# buck_boost.net
KiCad netlist of a schematic drawn in Altium Designer
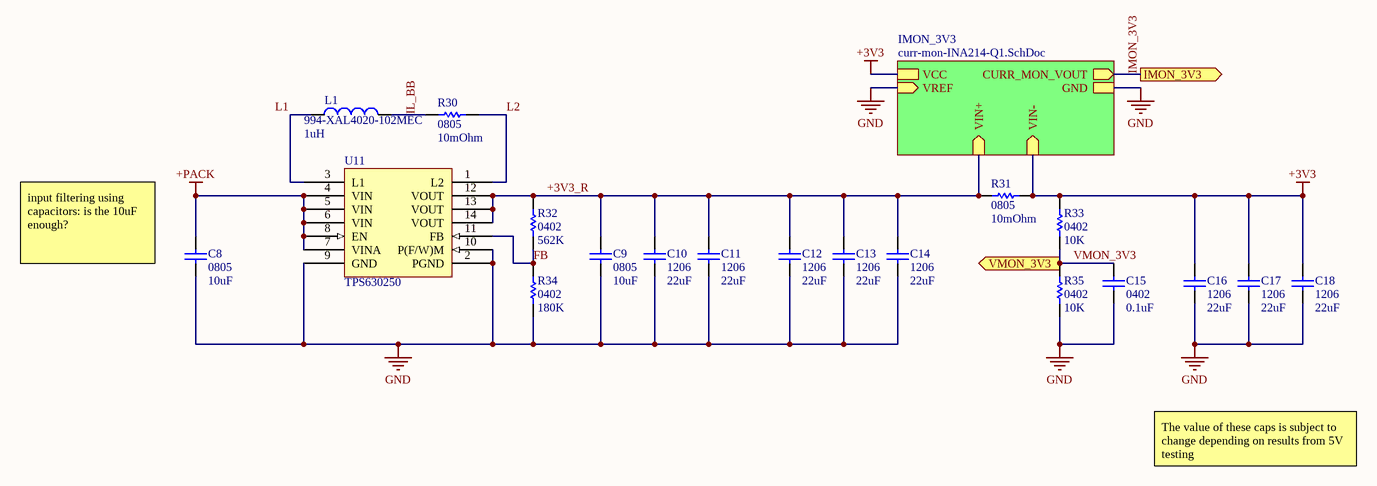
[diagram p0: buck_boost.SchDoc]

(export (version "E")
  (design (tool "Eeschema 10.0.6"))
  (components
    (comp (ref "C8")
      (value "0805")
      (footprint "CAP0805R")
      (description "0805 capacitor")
      (fields (field (name "ALTIUM_VALUE") "10uF"))
      (libsource (lib "heron-general") (part "CAP0805"))
    )
    (comp (ref "C9")
      (value "0805")
      (footprint "CAP0805R")
      (description "0805 capacitor")
      (fields (field (name "ALTIUM_VALUE") "10uF"))
      (libsource (lib "heron-general") (part "CAP0805"))
    )
    (comp (ref "C10")
      (value "1206")
      (footprint "CAP1206R")
      (description "1206 capacitor")
      (fields (field (name "ALTIUM_VALUE") "22uF"))
      (libsource (lib "heron-general") (part "CAP1206"))
    )
    (comp (ref "C11")
      (value "1206")
      (footprint "CAP1206R")
      (description "1206 capacitor")
      (fields (field (name "ALTIUM_VALUE") "22uF"))
      (libsource (lib "heron-general") (part "CAP1206"))
    )
    (comp (ref "C12")
      (value "1206")
      (footprint "CAP1206R")
      (description "1206 capacitor")
      (fields (field (name "ALTIUM_VALUE") "22uF"))
      (libsource (lib "heron-general") (part "CAP1206"))
    )
    (comp (ref "C13")
      (value "1206")
      (footprint "CAP1206R")
      (description "1206 capacitor")
      (fields (field (name "ALTIUM_VALUE") "22uF"))
      (libsource (lib "heron-general") (part "CAP1206"))
    )
    (comp (ref "C14")
      (value "1206")
      (footprint "CAP1206R")
      (description "1206 capacitor")
      (fields (field (name "ALTIUM_VALUE") "22uF"))
      (libsource (lib "heron-general") (part "CAP1206"))
    )
    (comp (ref "C15")
      (value "0402")
      (footprint "CAP0402R")
      (description "0402 capacitor")
      (fields (field (name "ALTIUM_VALUE") "0.1uF"))
      (libsource (lib "heron-general") (part "CAP0402"))
    )
    (comp (ref "C16")
      (value "1206")
      (footprint "CAP1206R")
      (description "1206 capacitor")
      (fields (field (name "ALTIUM_VALUE") "22uF"))
      (libsource (lib "heron-general") (part "CAP1206"))
    )
    (comp (ref "C17")
      (value "1206")
      (footprint "CAP1206R")
      (description "1206 capacitor")
      (fields (field (name "ALTIUM_VALUE") "22uF"))
      (libsource (lib "heron-general") (part "CAP1206"))
    )
    (comp (ref "C18")
      (value "1206")
      (footprint "CAP1206R")
      (description "1206 capacitor")
      (fields (field (name "ALTIUM_VALUE") "22uF"))
      (libsource (lib "heron-general") (part "CAP1206"))
    )
    (comp (ref "L1")
      (value "IND_XAL4020-102ME")
      (footprint "XAL4020-102ME")
      (description "1uH 20% 9.6A 14.60mOhms AEC-Q200")
      (fields
        (field (name "MANUFACTURER") "Coilcraft")
        (field (name "MANUFACTURER PART NUMBER") "XAL4020-102MEC")
        (field (name "INDUCTANCE") "1uH")
        (field (name "SUPPLIER PART NUMBER 1") "994-XAL4020-102MEC")
      )
      (libsource (lib "heron-general") (part "IND_XAL4020-102ME"))
    )
    (comp (ref "R30")
      (value "0805")
      (footprint "RES0805R")
      (description "0805 resistor")
      (fields
        (field (name "ALTIUM_VALUE") "10mOhm")
        (field (name "MANUFACTURER") "Panasonic")
        (field (name "MANUFACTURER PART NUMBER") "ERJ-8BWJR010V")
      )
      (libsource (lib "heron-general") (part "RES0805"))
    )
    (comp (ref "R31")
      (value "0805")
      (footprint "RES0805R")
      (description "0805 resistor")
      (fields
        (field (name "ALTIUM_VALUE") "10mOhm")
        (field (name "MANUFACTURER") "Panasonic")
        (field (name "MANUFACTURER PART NUMBER") "ERJ-8BWJR010V")
      )
      (libsource (lib "heron-general") (part "RES0805"))
    )
    (comp (ref "R32")
      (value "0402")
      (footprint "RES0402R")
      (description "0402 resistor")
      (fields (field (name "ALTIUM_VALUE") "562K"))
      (libsource (lib "heron-general") (part "RES0402"))
    )
    (comp (ref "R33")
      (value "0402")
      (footprint "RES0402R")
      (description "0402 resistor")
      (fields (field (name "ALTIUM_VALUE") "10K"))
      (libsource (lib "heron-general") (part "RES0402"))
    )
    (comp (ref "R34")
      (value "0402")
      (footprint "RES0402R")
      (description "0402 resistor")
      (fields (field (name "ALTIUM_VALUE") "180K"))
      (libsource (lib "heron-general") (part "RES0402"))
    )
    (comp (ref "R35")
      (value "0402")
      (footprint "RES0402R")
      (description "0402 resistor")
      (fields (field (name "ALTIUM_VALUE") "10K"))
      (libsource (lib "heron-general") (part "RES0402"))
    )
    (comp (ref "U11")
      (value "TPS630250")
      (footprint "RNC0014A")
      (description "Buck-boost converter")
      (libsource (lib "heron-general") (part "TPS630250"))
    )
  )
  (nets
    (net (code "1") (name "+3V3") (class "Default")
      (node (ref "C16") (pin "2") (pinfunction "2_2") (pintype "passive"))
      (node (ref "C17") (pin "2") (pinfunction "2_2") (pintype "passive"))
      (node (ref "C18") (pin "2") (pinfunction "2_2") (pintype "passive"))
      (node (ref "R31") (pin "2") (pinfunction "2_2") (pintype "passive"))
      (node (ref "R33") (pin "2") (pinfunction "2_2") (pintype "passive"))
    )
    (net (code "2") (name "+PACK") (class "Default")
      (node (ref "C8") (pin "2") (pinfunction "2_2") (pintype "passive"))
      (node (ref "U11") (pin "4") (pinfunction "VIN_4") (pintype "power_in"))
      (node (ref "U11") (pin "5") (pinfunction "VIN_5") (pintype "power_in"))
      (node (ref "U11") (pin "6") (pinfunction "VIN_6") (pintype "power_in"))
      (node (ref "U11") (pin "7") (pinfunction "VINA_7") (pintype "power_in"))
      (node (ref "U11") (pin "8") (pinfunction "EN_8") (pintype "input"))
    )
    (net (code "3") (name "/+3V3_R") (class "Default")
      (node (ref "C10") (pin "2") (pinfunction "2_2") (pintype "passive"))
      (node (ref "C11") (pin "2") (pinfunction "2_2") (pintype "passive"))
      (node (ref "C12") (pin "2") (pinfunction "2_2") (pintype "passive"))
      (node (ref "C13") (pin "2") (pinfunction "2_2") (pintype "passive"))
      (node (ref "C14") (pin "2") (pinfunction "2_2") (pintype "passive"))
      (node (ref "C9") (pin "2") (pinfunction "2_2") (pintype "passive"))
      (node (ref "R31") (pin "1") (pinfunction "1_1") (pintype "passive"))
      (node (ref "R32") (pin "2") (pinfunction "2_2") (pintype "passive"))
      (node (ref "U11") (pin "12") (pinfunction "VOUT_12") (pintype "passive"))
      (node (ref "U11") (pin "13") (pinfunction "VOUT_13") (pintype "passive"))
      (node (ref "U11") (pin "14") (pinfunction "VOUT_14") (pintype "passive"))
    )
    (net (code "4") (name "/FB") (class "Default")
      (node (ref "R32") (pin "1") (pinfunction "1_1") (pintype "passive"))
      (node (ref "R34") (pin "2") (pinfunction "2_2") (pintype "passive"))
      (node (ref "U11") (pin "11") (pinfunction "FB_11") (pintype "input"))
    )
    (net (code "5") (name "/IL_BB") (class "Default")
      (node (ref "L1") (pin "2") (pinfunction "2_2") (pintype "passive"))
      (node (ref "R30") (pin "1") (pinfunction "1_1") (pintype "passive"))
    )
    (net (code "7") (name "/L1") (class "Default")
      (node (ref "L1") (pin "1") (pinfunction "1_1") (pintype "passive"))
      (node (ref "U11") (pin "3") (pinfunction "L1_3") (pintype "power_in"))
    )
    (net (code "8") (name "/L2") (class "Default")
      (node (ref "R30") (pin "2") (pinfunction "2_2") (pintype "passive"))
      (node (ref "U11") (pin "1") (pinfunction "L2_1") (pintype "power_in"))
    )
    (net (code "9") (name "/VMON_3V3") (class "Default")
      (node (ref "C15") (pin "2") (pinfunction "2_2") (pintype "passive"))
      (node (ref "R33") (pin "1") (pinfunction "1_1") (pintype "passive"))
      (node (ref "R35") (pin "2") (pinfunction "2_2") (pintype "passive"))
    )
    (net (code "10") (name "GND") (class "Default")
      (node (ref "C10") (pin "1") (pinfunction "1_1") (pintype "passive"))
      (node (ref "C11") (pin "1") (pinfunction "1_1") (pintype "passive"))
      (node (ref "C12") (pin "1") (pinfunction "1_1") (pintype "passive"))
      (node (ref "C13") (pin "1") (pinfunction "1_1") (pintype "passive"))
      (node (ref "C14") (pin "1") (pinfunction "1_1") (pintype "passive"))
      (node (ref "C15") (pin "1") (pinfunction "1_1") (pintype "passive"))
      (node (ref "C16") (pin "1") (pinfunction "1_1") (pintype "passive"))
      (node (ref "C17") (pin "1") (pinfunction "1_1") (pintype "passive"))
      (node (ref "C18") (pin "1") (pinfunction "1_1") (pintype "passive"))
      (node (ref "C8") (pin "1") (pinfunction "1_1") (pintype "passive"))
      (node (ref "C9") (pin "1") (pinfunction "1_1") (pintype "passive"))
      (node (ref "R34") (pin "1") (pinfunction "1_1") (pintype "passive"))
      (node (ref "R35") (pin "1") (pinfunction "1_1") (pintype "passive"))
      (node (ref "U11") (pin "10") (pinfunction "P(F/W)M_10") (pintype "input"))
      (node (ref "U11") (pin "2") (pinfunction "PGND_2") (pintype "power_in"))
      (node (ref "U11") (pin "9") (pinfunction "GND_9") (pintype "power_in"))
    )
  )
)
